# FPGA_Bypass_1V2.net
KiCad netlist of a schematic drawn in Altium Designer
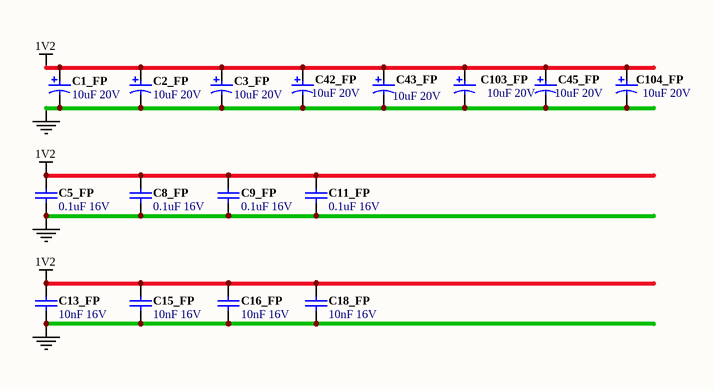
[diagram p0: FPGA_Bypass_1V2.SCHDOC]

(export (version "E")
  (design (tool "Eeschema 10.0.6"))
  (components
    (comp (ref "C1_FP")
      (value "10uF 20V")
      (footprint "CAPC3528-STAR")
      (description "Capacitor, Tantalum, 10uF 10% 20V MCCT-B (3528)")
      (fields (field (name "TOLERANCE") "10 %"))
      (libsource (lib "altium-import") (part "root_0_CAP-P_"))
    )
    (comp (ref "C2_FP")
      (value "10uF 20V")
      (footprint "CAPC3528-STAR")
      (description "Capacitor, Tantalum, 10uF 10% 20V MCCT-B (3528)")
      (fields (field (name "TOLERANCE") "10 %"))
      (libsource (lib "altium-import") (part "root_0_CAP-P_"))
    )
    (comp (ref "C3_FP")
      (value "10uF 20V")
      (footprint "CAPC3528-STAR")
      (description "Capacitor, Tantalum, 10uF 10% 20V MCCT-B (3528)")
      (fields (field (name "TOLERANCE") "10 %"))
      (libsource (lib "altium-import") (part "root_0_CAP-P_"))
    )
    (comp (ref "C5_FP")
      (value "0.1uF 16V")
      (footprint "CAPC1005-STAR")
      (description "Capacitor, Ceramic, 0.1uF 10% 16V 0402 (1005) X7R")
      (fields (field (name "TOLERANCE") "10 %"))
      (libsource (lib "altium-import") (part "root_0_mirrored_CAP-NP_"))
    )
    (comp (ref "C8_FP")
      (value "0.1uF 16V")
      (footprint "CAPC1005-STAR")
      (description "Capacitor, Ceramic, 0.1uF 10% 16V 0402 (1005) X7R")
      (fields (field (name "TOLERANCE") "10 %"))
      (libsource (lib "altium-import") (part "root_0_mirrored_CAP-NP_"))
    )
    (comp (ref "C9_FP")
      (value "0.1uF 16V")
      (footprint "CAPC1005-STAR")
      (description "Capacitor, Ceramic, 0.1uF 10% 16V 0402 (1005) X7R")
      (fields (field (name "TOLERANCE") "10 %"))
      (libsource (lib "altium-import") (part "root_0_mirrored_CAP-NP_"))
    )
    (comp (ref "C11_FP")
      (value "0.1uF 16V")
      (footprint "CAPC1005-STAR")
      (description "Capacitor, Ceramic, 0.1uF 10% 16V 0402 (1005) X7R")
      (fields (field (name "TOLERANCE") "10 %"))
      (libsource (lib "altium-import") (part "root_0_mirrored_CAP-NP_"))
    )
    (comp (ref "C13_FP")
      (value "10nF 16V")
      (footprint "CAPC1005-STAR")
      (description "Capacitor, Ceramic, 10nF 10% 16V 0402 (1005) X7R")
      (fields (field (name "TOLERANCE") "10 %"))
      (libsource (lib "altium-import") (part "root_0_CAP-NP_"))
    )
    (comp (ref "C15_FP")
      (value "10nF 16V")
      (footprint "CAPC1005-STAR")
      (description "Capacitor, Ceramic, 10nF 10% 16V 0402 (1005) X7R")
      (fields (field (name "TOLERANCE") "10 %"))
      (libsource (lib "altium-import") (part "root_0_CAP-NP_"))
    )
    (comp (ref "C16_FP")
      (value "10nF 16V")
      (footprint "CAPC1005-STAR")
      (description "Capacitor, Ceramic, 10nF 10% 16V 0402 (1005) X7R")
      (fields (field (name "TOLERANCE") "10 %"))
      (libsource (lib "altium-import") (part "root_0_CAP-NP_"))
    )
    (comp (ref "C18_FP")
      (value "10nF 16V")
      (footprint "CAPC1005-STAR")
      (description "Capacitor, Ceramic, 10nF 10% 16V 0402 (1005) X7R")
      (fields (field (name "TOLERANCE") "10 %"))
      (libsource (lib "altium-import") (part "root_0_CAP-NP_"))
    )
    (comp (ref "C42_FP")
      (value "10uF 20V")
      (footprint "CAPC3528-STAR")
      (description "Capacitor, Tantalum, 10uF 10% 20V MCCT-B (3528)")
      (fields (field (name "TOLERANCE") "10 %"))
      (libsource (lib "altium-import") (part "root_0_CAP-P_"))
    )
    (comp (ref "C43_FP")
      (value "10uF 20V")
      (footprint "CAPC3528-STAR")
      (description "Capacitor, Tantalum, 10uF 10% 20V MCCT-B (3528)")
      (fields (field (name "TOLERANCE") "10 %"))
      (libsource (lib "altium-import") (part "root_0_CAP-P_"))
    )
    (comp (ref "C45_FP")
      (value "10uF 20V")
      (footprint "CAPC3528-STAR")
      (description "Capacitor, Tantalum, 10uF 10% 20V MCCT-B (3528)")
      (fields (field (name "TOLERANCE") "10 %"))
      (libsource (lib "altium-import") (part "root_0_CAP-P_"))
    )
    (comp (ref "C103_FP")
      (value "10uF 20V")
      (footprint "CAPC3528-STAR")
      (description "Capacitor, Tantalum, 10uF 10% 20V MCCT-B (3528)")
      (fields (field (name "TOLERANCE") "10 %"))
      (libsource (lib "altium-import") (part "root_0_CAP-P_"))
    )
    (comp (ref "C104_FP")
      (value "10uF 20V")
      (footprint "CAPC3528-STAR")
      (description "Capacitor, Tantalum, 10uF 10% 20V MCCT-B (3528)")
      (fields (field (name "TOLERANCE") "10 %"))
      (libsource (lib "altium-import") (part "root_0_CAP-P_"))
    )
  )
  (nets
    (net (code "1") (name "1V2") (class "Default")
      (node (ref "C103_FP") (pin "1") (pinfunction "1_1") (pintype "passive"))
      (node (ref "C104_FP") (pin "1") (pinfunction "1_1") (pintype "passive"))
      (node (ref "C11_FP") (pin "1") (pinfunction "1_1") (pintype "passive"))
      (node (ref "C13_FP") (pin "1") (pinfunction "1_1") (pintype "passive"))
      (node (ref "C15_FP") (pin "1") (pinfunction "1_1") (pintype "passive"))
      (node (ref "C16_FP") (pin "1") (pinfunction "1_1") (pintype "passive"))
      (node (ref "C18_FP") (pin "1") (pinfunction "1_1") (pintype "passive"))
      (node (ref "C1_FP") (pin "1") (pinfunction "1_1") (pintype "passive"))
      (node (ref "C2_FP") (pin "1") (pinfunction "1_1") (pintype "passive"))
      (node (ref "C3_FP") (pin "1") (pinfunction "1_1") (pintype "passive"))
      (node (ref "C42_FP") (pin "1") (pinfunction "1_1") (pintype "passive"))
      (node (ref "C43_FP") (pin "1") (pinfunction "1_1") (pintype "passive"))
      (node (ref "C45_FP") (pin "1") (pinfunction "1_1") (pintype "passive"))
      (node (ref "C5_FP") (pin "1") (pinfunction "1_1") (pintype "passive"))
      (node (ref "C8_FP") (pin "1") (pinfunction "1_1") (pintype "passive"))
      (node (ref "C9_FP") (pin "1") (pinfunction "1_1") (pintype "passive"))
    )
    (net (code "2") (name "GND") (class "Default")
      (node (ref "C103_FP") (pin "2") (pinfunction "2_2") (pintype "passive"))
      (node (ref "C104_FP") (pin "2") (pinfunction "2_2") (pintype "passive"))
      (node (ref "C11_FP") (pin "2") (pinfunction "2_2") (pintype "passive"))
      (node (ref "C13_FP") (pin "2") (pinfunction "2_2") (pintype "passive"))
      (node (ref "C15_FP") (pin "2") (pinfunction "2_2") (pintype "passive"))
      (node (ref "C16_FP") (pin "2") (pinfunction "2_2") (pintype "passive"))
      (node (ref "C18_FP") (pin "2") (pinfunction "2_2") (pintype "passive"))
      (node (ref "C1_FP") (pin "2") (pinfunction "2_2") (pintype "passive"))
      (node (ref "C2_FP") (pin "2") (pinfunction "2_2") (pintype "passive"))
      (node (ref "C3_FP") (pin "2") (pinfunction "2_2") (pintype "passive"))
      (node (ref "C42_FP") (pin "2") (pinfunction "2_2") (pintype "passive"))
      (node (ref "C43_FP") (pin "2") (pinfunction "2_2") (pintype "passive"))
      (node (ref "C45_FP") (pin "2") (pinfunction "2_2") (pintype "passive"))
      (node (ref "C5_FP") (pin "2") (pinfunction "2_2") (pintype "passive"))
      (node (ref "C8_FP") (pin "2") (pinfunction "2_2") (pintype "passive"))
      (node (ref "C9_FP") (pin "2") (pinfunction "2_2") (pintype "passive"))
    )
  )
)
